# schemat.net
KiCad netlist of a schematic drawn in Altium Designer
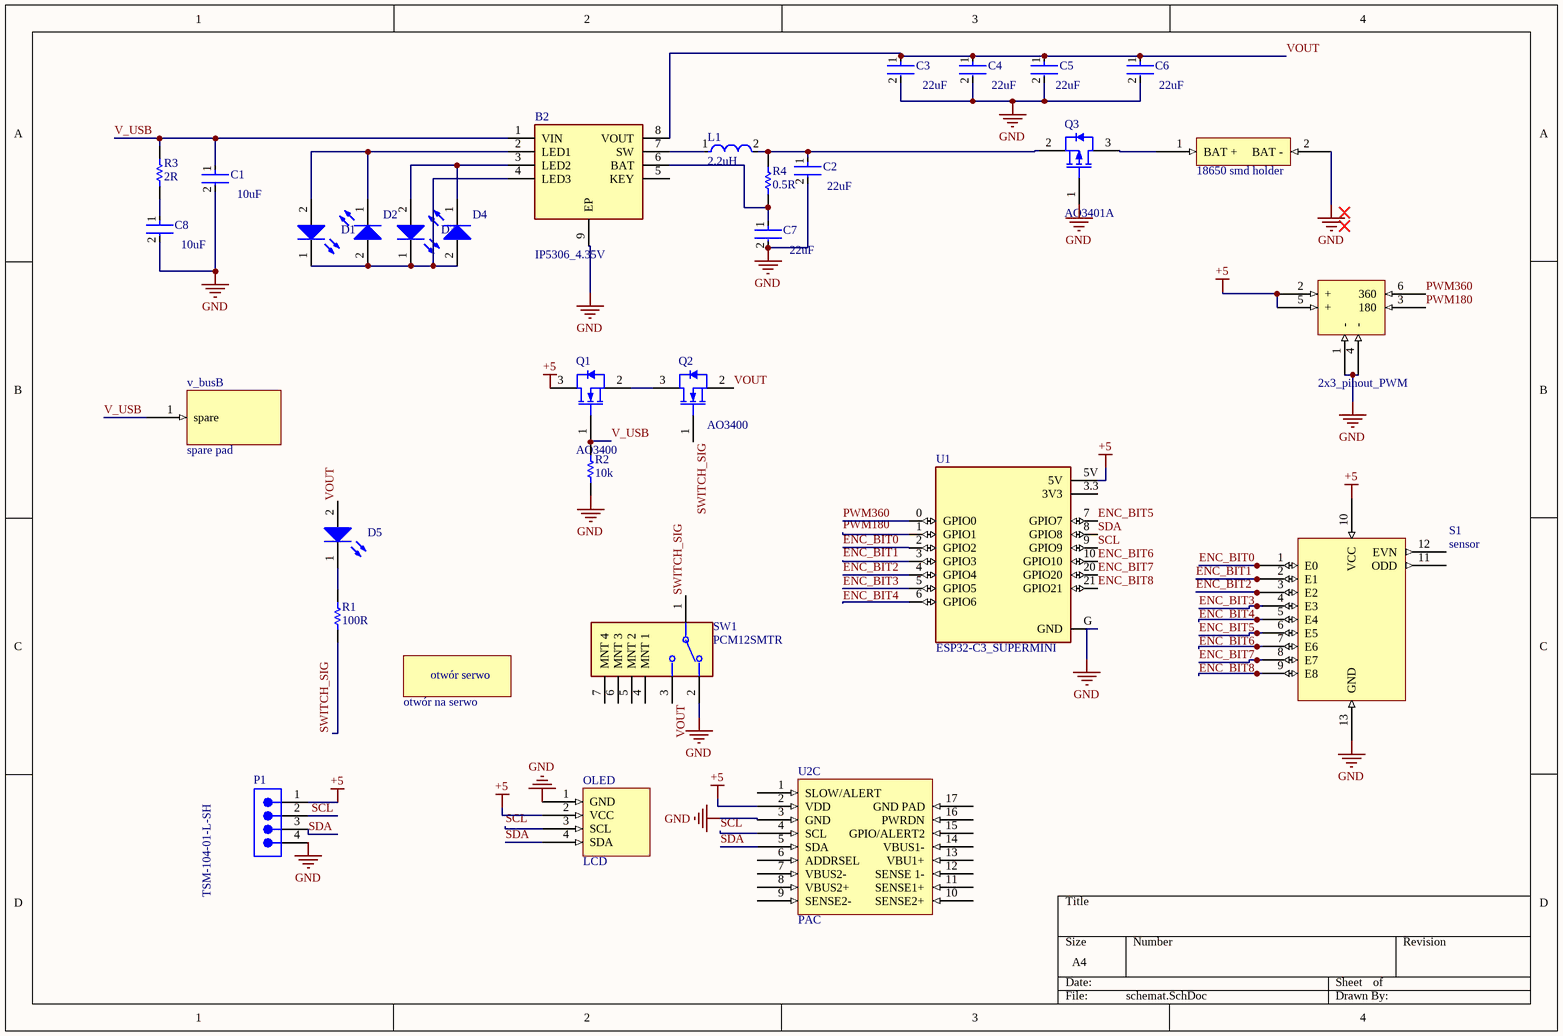
[diagram p0: schemat.SchDoc]

(export (version "E")
  (design (tool "Eeschema 10.0.6"))
  (components
    (comp (ref "*")
      (value "otwór na serwo")
      (footprint "serwo")
      (libsource (lib "biblioteka") (part "otwór na serwo"))
    )
    (comp (ref "B1")
      (value "18650 smd holder")
      (footprint "18650 smd holder")
      (libsource (lib "schematy") (part "18650 smd holder"))
    )
    (comp (ref "B2")
      (value "IP5306_4.35V")
      (footprint "SOIC127P600X165-9N")
      (description "2.1A Charging 2.4 A Discharge Highly Integrated Mobile Power Supply")
      (libsource (lib "IP5306_4.35V") (part "IP5306_4.35V"))
    )
    (comp (ref "C1")
      (value "10uF")
      (footprint "FP-GRM21B-0_15-MFG")
      (description "Chip Multilayer Ceramic Capacitors for General Purpose, 0805, 22uF, X5R, 15%, 20%, 6.3V")
      (fields (field (name "VOLTAGE") "6.3V") (field (name "TOLERANCE") "20%"))
      (libsource (lib "Altium Content Vault") (part "b4654b650e69147ec39a6b967a45e02"))
    )
    (comp (ref "C2")
      (value "22uF")
      (footprint "FP-GRM21B-0_15-MFG")
      (description "Chip Multilayer Ceramic Capacitors for General Purpose, 0805, 22uF, X5R, 15%, 20%, 6.3V")
      (fields (field (name "VOLTAGE") "6.3V") (field (name "TOLERANCE") "20%"))
      (libsource (lib "Altium Content Vault") (part "b4654b650e69147ec39a6b967a45e02"))
    )
    (comp (ref "C3")
      (value "22uF")
      (footprint "FP-GRM21B-0_15-MFG")
      (description "Chip Multilayer Ceramic Capacitors for General Purpose, 0805, 22uF, X5R, 15%, 20%, 6.3V")
      (fields (field (name "VOLTAGE") "6.3V") (field (name "TOLERANCE") "20%"))
      (libsource (lib "Altium Content Vault") (part "b4654b650e69147ec39a6b967a45e02"))
    )
    (comp (ref "C4")
      (value "22uF")
      (footprint "FP-GRM21B-0_15-MFG")
      (description "Chip Multilayer Ceramic Capacitors for General Purpose, 0805, 22uF, X5R, 15%, 20%, 6.3V")
      (fields (field (name "VOLTAGE") "6.3V") (field (name "TOLERANCE") "20%"))
      (libsource (lib "Altium Content Vault") (part "b4654b650e69147ec39a6b967a45e02"))
    )
    (comp (ref "C5")
      (value "22uF")
      (footprint "FP-GRM21B-0_15-MFG")
      (description "Chip Multilayer Ceramic Capacitors for General Purpose, 0805, 22uF, X5R, 15%, 20%, 6.3V")
      (fields (field (name "VOLTAGE") "6.3V") (field (name "TOLERANCE") "20%"))
      (libsource (lib "Altium Content Vault") (part "b4654b650e69147ec39a6b967a45e02"))
    )
    (comp (ref "C6")
      (value "22uF")
      (footprint "FP-GRM21B-0_15-MFG")
      (description "Chip Multilayer Ceramic Capacitors for General Purpose, 0805, 22uF, X5R, 15%, 20%, 6.3V")
      (fields (field (name "VOLTAGE") "6.3V") (field (name "TOLERANCE") "20%"))
      (libsource (lib "Altium Content Vault") (part "b4654b650e69147ec39a6b967a45e02"))
    )
    (comp (ref "C7")
      (value "22uF")
      (footprint "FP-GRM21B-0_15-MFG")
      (description "Chip Multilayer Ceramic Capacitors for General Purpose, 0805, 22uF, X5R, 15%, 20%, 6.3V")
      (fields (field (name "VOLTAGE") "6.3V") (field (name "TOLERANCE") "20%"))
      (libsource (lib "Altium Content Vault") (part "b4654b650e69147ec39a6b967a45e02"))
    )
    (comp (ref "C8")
      (value "10uF")
      (footprint "FP-GRM21B-0_15-MFG")
      (description "Chip Multilayer Ceramic Capacitors for General Purpose, 0805, 22uF, X5R, 15%, 20%, 6.3V")
      (fields (field (name "VOLTAGE") "6.3V") (field (name "TOLERANCE") "20%"))
      (libsource (lib "Altium Content Vault") (part "b4654b650e69147ec39a6b967a45e02"))
    )
    (comp (ref "D1")
      (value "150120BS75000")
      (footprint "WL-SMCW_1206_150120xx75000")
      (libsource (lib "Altium Content Vault") (part "LED_Blue_2A-1K"))
    )
    (comp (ref "D2")
      (value "150120BS75000")
      (footprint "WL-SMCW_1206_150120xx75000")
      (libsource (lib "Altium Content Vault") (part "LED_Blue_2A-1K"))
    )
    (comp (ref "D3")
      (value "150120BS75000")
      (footprint "WL-SMCW_1206_150120xx75000")
      (libsource (lib "Altium Content Vault") (part "LED_Blue_2A-1K"))
    )
    (comp (ref "D4")
      (value "150120BS75000")
      (footprint "WL-SMCW_1206_150120xx75000")
      (libsource (lib "Altium Content Vault") (part "LED_Blue_2A-1K"))
    )
    (comp (ref "D5")
      (value "150120BS75000")
      (footprint "WL-SMCW_1206_150120xx75000")
      (libsource (lib "Altium Content Vault") (part "LED_Blue_2A-1K"))
    )
    (comp (ref "J1")
      (value "2x3_pinout_PWM")
      (footprint "Goldpin raster 2x3")
      (libsource (lib "biblioteka") (part "2x3_pinout_PWM"))
    )
    (comp (ref "L1")
      (value "2.2uH")
      (footprint "FP-ASPI-0630LR-MFG")
      (description "FIXED IND 10UH 4A 68 MOHM SMD")
      (fields (field (name "TOLERANCE") "20%"))
      (libsource (lib "Altium Content Vault") (part "725321dda6339637d4d059423bc1c3c"))
    )
    (comp (ref "OLED") (value "LCD") (footprint "LCD") (libsource (lib "schematy") (part "LCD")))
    (comp (ref "P1")
      (value "TSM-104-01-L-SH")
      (footprint "SMTC-TSM-104-01-X-SH")
      (fields (field (name "MANUFACTURER") "Samtec"))
      (libsource (lib "Altium Content Vault") (part "SMTC-TSM-104-01-X-SH"))
    )
    (comp (ref "Q1")
      (value "AO3400")
      (footprint "AO-SOT23-3_V")
      (description "N-channel Enhancement Mode Field-Effect Transistor; 5.8A/30V")
      (fields (field (name "MANUFACTURER") "Alpha and Omega"))
      (libsource (lib "Altium Content Vault") (part "AO-NEMOS-G1S2D3-3"))
    )
    (comp (ref "Q2")
      (value "AO3400")
      (footprint "AO-SOT23-3_V")
      (description "N-channel Enhancement Mode Field-Effect Transistor; 5.8A/30V")
      (fields (field (name "MANUFACTURER") "Alpha and Omega"))
      (libsource (lib "Altium Content Vault") (part "AO-NEMOS-G1S2D3-3"))
    )
    (comp (ref "Q3")
      (value "AO3401A")
      (footprint "AO-SOT-23-3L_V")
      (description "P-Channel MOSFET, 30 V, 4 A, -55 to 150 degC, 3-Pin SOT-23-3L, RoHS, Tape and Reel")
      (fields (field (name "MANUFACTURER") "Alpha and Omega"))
      (libsource (lib "Altium Content Vault") (part "PEMOS-GSD-3"))
    )
    (comp (ref "R1")
      (value "100R")
      (footprint "RESC2013X50X30LL20T20")
      (fields (field (name "MANUFACTURER") "Vishay Dale") (field (name "PART NUMBER") "CRCW08050000Z0EA"))
      (libsource (lib "Altium Content Vault") (part "RES"))
    )
    (comp (ref "R2")
      (value "10k")
      (footprint "RESC2013X50X30LL20T20")
      (fields (field (name "MANUFACTURER") "Vishay Dale") (field (name "PART NUMBER") "CRCW08050000Z0EA"))
      (libsource (lib "Altium Content Vault") (part "RES"))
    )
    (comp (ref "R3")
      (value "2R")
      (footprint "RESC2013X50X30LL20T20")
      (fields (field (name "MANUFACTURER") "Vishay Dale") (field (name "PART NUMBER") "CRCW08050000Z0EA"))
      (libsource (lib "Altium Content Vault") (part "RES"))
    )
    (comp (ref "R4")
      (value "0.5R")
      (footprint "RESC2013X50X30LL20T20")
      (fields (field (name "MANUFACTURER") "Vishay Dale") (field (name "PART NUMBER") "CRCW08050000Z0EA"))
      (libsource (lib "Altium Content Vault") (part "RES"))
    )
    (comp (ref "S1")
      (value "sensor")
      (footprint "czujnik zbliżeniowy")
      (libsource (lib "schematy") (part "sensor"))
    )
    (comp (ref "SW1")
      (value "PCM12SMTR")
      (footprint "FP-PCM12SMTR-MFG")
      (description "SWITCH SLIDE SPDT 300MA 6V")
      (libsource (lib "Altium Content Vault") (part "1a3f67d7e2b5469b171eeab59ffb4d2"))
    )
    (comp (ref "U1")
      (value "ESP32-C3_SUPERMINI")
      (footprint "MODULE_ESP32-C3_SUPERMINI")
      (description "Super tiny ESP32-C3 board")
      (fields (field (name "MF") "Espressif Systems") (field (name "MP") "ESP32-C3 SuperMini"))
      (libsource (lib "biblioteka") (part "ESP32-C3_SUPERMINI"))
    )
    (comp (ref "U2")
      (value "PAC")
      (footprint "QFN50P300X300X90_HS-17N")
      (libsource (lib "schematy") (part "PAC"))
    )
    (comp (ref "v_bus")
      (value "spare pad")
      (footprint "spare pad")
      (libsource (lib "schematy") (part "spare pad"))
    )
  )
  (nets
    (net (code "1") (name "+5") (class "Default")
      (node (ref "J1") (pin "2") (pinfunction "+_2") (pintype "input"))
      (node (ref "J1") (pin "5") (pinfunction "+_5") (pintype "input"))
      (node (ref "OLED") (pin "2") (pinfunction "VCC_2") (pintype "input"))
      (node (ref "P1") (pin "1") (pinfunction "1_1") (pintype "passive"))
      (node (ref "Q1") (pin "3") (pinfunction "D_3") (pintype "passive"))
      (node (ref "S1") (pin "10") (pinfunction "VCC_10") (pintype "input"))
      (node (ref "U1") (pin "5V") (pinfunction "5V_5V") (pintype "power_in"))
      (node (ref "U2") (pin "2") (pinfunction "VDD_2") (pintype "input"))
    )
    (net (code "2") (name "/ENC_BIT0") (class "Default")
      (node (ref "S1") (pin "1") (pinfunction "E0_1") (pintype "bidirectional"))
      (node (ref "U1") (pin "2") (pinfunction "GPIO2_2") (pintype "bidirectional"))
    )
    (net (code "3") (name "/ENC_BIT1") (class "Default")
      (node (ref "S1") (pin "2") (pinfunction "E1_2") (pintype "bidirectional"))
      (node (ref "U1") (pin "3") (pinfunction "GPIO3_3") (pintype "bidirectional"))
    )
    (net (code "4") (name "/ENC_BIT2") (class "Default")
      (node (ref "S1") (pin "3") (pinfunction "E2_3") (pintype "bidirectional"))
      (node (ref "U1") (pin "4") (pinfunction "GPIO4_4") (pintype "bidirectional"))
    )
    (net (code "5") (name "/ENC_BIT3") (class "Default")
      (node (ref "S1") (pin "4") (pinfunction "E3_4") (pintype "bidirectional"))
      (node (ref "U1") (pin "5") (pinfunction "GPIO5_5") (pintype "bidirectional"))
    )
    (net (code "6") (name "/ENC_BIT4") (class "Default")
      (node (ref "S1") (pin "5") (pinfunction "E4_5") (pintype "bidirectional"))
      (node (ref "U1") (pin "6") (pinfunction "GPIO6_6") (pintype "bidirectional"))
    )
    (net (code "7") (name "/ENC_BIT5") (class "Default")
      (node (ref "S1") (pin "6") (pinfunction "E5_6") (pintype "bidirectional"))
      (node (ref "U1") (pin "7") (pinfunction "GPIO7_7") (pintype "bidirectional"))
    )
    (net (code "8") (name "/ENC_BIT6") (class "Default")
      (node (ref "S1") (pin "7") (pinfunction "E6_7") (pintype "bidirectional"))
      (node (ref "U1") (pin "10") (pinfunction "GPIO10_10") (pintype "bidirectional"))
    )
    (net (code "9") (name "/ENC_BIT7") (class "Default")
      (node (ref "S1") (pin "8") (pinfunction "E7_8") (pintype "bidirectional"))
      (node (ref "U1") (pin "20") (pinfunction "GPIO20_20") (pintype "bidirectional"))
    )
    (net (code "10") (name "/ENC_BIT8") (class "Default")
      (node (ref "S1") (pin "9") (pinfunction "E8_9") (pintype "bidirectional"))
      (node (ref "U1") (pin "21") (pinfunction "GPIO21_21") (pintype "bidirectional"))
    )
    (net (code "11") (name "/PWM180") (class "Default")
      (node (ref "J1") (pin "3") (pinfunction "180_3") (pintype "input"))
      (node (ref "U1") (pin "1") (pinfunction "GPIO1_1") (pintype "bidirectional"))
    )
    (net (code "12") (name "/PWM360") (class "Default")
      (node (ref "J1") (pin "6") (pinfunction "360_6") (pintype "input"))
      (node (ref "U1") (pin "0") (pinfunction "GPIO0_0") (pintype "bidirectional"))
    )
    (net (code "13") (name "/SCL") (class "Default")
      (node (ref "OLED") (pin "3") (pinfunction "SCL_3") (pintype "input"))
      (node (ref "P1") (pin "2") (pinfunction "2_2") (pintype "passive"))
      (node (ref "U1") (pin "9") (pinfunction "GPIO9_9") (pintype "bidirectional"))
      (node (ref "U2") (pin "4") (pinfunction "SCL_4") (pintype "input"))
    )
    (net (code "14") (name "/SDA") (class "Default")
      (node (ref "OLED") (pin "4") (pinfunction "SDA_4") (pintype "input"))
      (node (ref "P1") (pin "3") (pinfunction "3_3") (pintype "passive"))
      (node (ref "U1") (pin "8") (pinfunction "GPIO8_8") (pintype "bidirectional"))
      (node (ref "U2") (pin "5") (pinfunction "SDA_5") (pintype "input"))
    )
    (net (code "15") (name "/SWITCH_SIG") (class "Default")
      (node (ref "Q2") (pin "1") (pinfunction "G_1") (pintype "passive"))
      (node (ref "R1") (pin "2") (pinfunction "2_2") (pintype "passive"))
      (node (ref "SW1") (pin "1") (pinfunction "1_1") (pintype "passive"))
    )
    (net (code "16") (name "/VOUT") (class "Default")
      (node (ref "B2") (pin "8") (pinfunction "VOUT_8") (pintype "passive"))
      (node (ref "C3") (pin "1") (pinfunction "1_1") (pintype "passive"))
      (node (ref "C4") (pin "1") (pinfunction "1_1") (pintype "passive"))
      (node (ref "C5") (pin "1") (pinfunction "1_1") (pintype "passive"))
      (node (ref "C6") (pin "1") (pinfunction "1_1") (pintype "passive"))
      (node (ref "D5") (pin "2") (pinfunction "A_2") (pintype "passive"))
      (node (ref "Q2") (pin "2") (pinfunction "S_2") (pintype "passive"))
      (node (ref "SW1") (pin "3") (pinfunction "3_3") (pintype "passive"))
    )
    (net (code "17") (name "/V_USB") (class "Default")
      (node (ref "B2") (pin "1") (pinfunction "VIN_1") (pintype "passive"))
      (node (ref "C1") (pin "1") (pinfunction "1_1") (pintype "passive"))
      (node (ref "Q1") (pin "1") (pinfunction "G_1") (pintype "passive"))
      (node (ref "R2") (pin "2") (pinfunction "2_2") (pintype "passive"))
      (node (ref "R3") (pin "1") (pinfunction "1_1") (pintype "passive"))
      (node (ref "v_bus") (pin "1") (pinfunction "spare_1") (pintype "input"))
    )
    (net (code "18") (name "GND") (class "Default")
      (node (ref "B1") (pin "2") (pinfunction "BAT_-_2") (pintype "input"))
      (node (ref "B2") (pin "9") (pinfunction "EP_9") (pintype "passive"))
      (node (ref "C1") (pin "2") (pinfunction "2_2") (pintype "passive"))
      (node (ref "C2") (pin "2") (pinfunction "2_2") (pintype "passive"))
      (node (ref "C3") (pin "2") (pinfunction "2_2") (pintype "passive"))
      (node (ref "C4") (pin "2") (pinfunction "2_2") (pintype "passive"))
      (node (ref "C5") (pin "2") (pinfunction "2_2") (pintype "passive"))
      (node (ref "C6") (pin "2") (pinfunction "2_2") (pintype "passive"))
      (node (ref "C7") (pin "2") (pinfunction "2_2") (pintype "passive"))
      (node (ref "C8") (pin "2") (pinfunction "2_2") (pintype "passive"))
      (node (ref "J1") (pin "1") (pinfunction "-_1") (pintype "input"))
      (node (ref "J1") (pin "4") (pinfunction "-_4") (pintype "input"))
      (node (ref "OLED") (pin "1") (pinfunction "GND_1") (pintype "input"))
      (node (ref "Q3") (pin "1") (pinfunction "GATE_1") (pintype "passive"))
      (node (ref "R2") (pin "1") (pinfunction "1_1") (pintype "passive"))
      (node (ref "S1") (pin "13") (pinfunction "GND_13") (pintype "input"))
      (node (ref "SW1") (pin "2") (pinfunction "2_2") (pintype "passive"))
      (node (ref "U1") (pin "G") (pinfunction "GND_G") (pintype "power_in"))
      (node (ref "U2") (pin "3") (pinfunction "GND_3") (pintype "input"))
    )
    (net (code "19") (name "Net-(B1-BAT_+)") (class "Default")
      (node (ref "B1") (pin "1") (pinfunction "BAT_+_1") (pintype "input"))
      (node (ref "Q3") (pin "3") (pinfunction "DRAIN_3") (pintype "passive"))
    )
    (net (code "20") (name "Net-(B2-BAT)") (class "Default")
      (node (ref "B2") (pin "6") (pinfunction "BAT_6") (pintype "passive"))
      (node (ref "C7") (pin "1") (pinfunction "1_1") (pintype "passive"))
      (node (ref "R4") (pin "2") (pinfunction "2_2") (pintype "passive"))
    )
    (net (code "21") (name "Net-(B2-LED1)") (class "Default")
      (node (ref "B2") (pin "2") (pinfunction "LED1_2") (pintype "passive"))
      (node (ref "D1") (pin "2") (pinfunction "A_2") (pintype "passive"))
      (node (ref "D2") (pin "1") (pinfunction "K_1") (pintype "passive"))
    )
    (net (code "22") (name "Net-(B2-LED2)") (class "Default")
      (node (ref "B2") (pin "3") (pinfunction "LED2_3") (pintype "passive"))
      (node (ref "D3") (pin "2") (pinfunction "A_2") (pintype "passive"))
      (node (ref "D4") (pin "1") (pinfunction "K_1") (pintype "passive"))
    )
    (net (code "23") (name "Net-(B2-LED3)") (class "Default")
      (node (ref "B2") (pin "4") (pinfunction "LED3_4") (pintype "passive"))
      (node (ref "D1") (pin "1") (pinfunction "K_1") (pintype "passive"))
      (node (ref "D2") (pin "2") (pinfunction "A_2") (pintype "passive"))
      (node (ref "D3") (pin "1") (pinfunction "K_1") (pintype "passive"))
      (node (ref "D4") (pin "2") (pinfunction "A_2") (pintype "passive"))
    )
    (net (code "24") (name "Net-(B2-SW)") (class "Default")
      (node (ref "B2") (pin "7") (pinfunction "SW_7") (pintype "passive"))
      (node (ref "L1") (pin "1") (pinfunction "1_1") (pintype "passive"))
    )
    (net (code "25") (name "Net-(C8-Pad1)") (class "Default")
      (node (ref "C8") (pin "1") (pinfunction "1_1") (pintype "passive"))
      (node (ref "R3") (pin "2") (pinfunction "2_2") (pintype "passive"))
    )
    (net (code "26") (name "Net-(D5-K)") (class "Default")
      (node (ref "D5") (pin "1") (pinfunction "K_1") (pintype "passive"))
      (node (ref "R1") (pin "1") (pinfunction "1_1") (pintype "passive"))
    )
    (net (code "27") (name "Net-(Q1-S)") (class "Default")
      (node (ref "Q1") (pin "2") (pinfunction "S_2") (pintype "passive"))
      (node (ref "Q2") (pin "3") (pinfunction "D_3") (pintype "passive"))
    )
    (net (code "28") (name "Net-(Q3-SOURCE)") (class "Default")
      (node (ref "C2") (pin "1") (pinfunction "1_1") (pintype "passive"))
      (node (ref "L1") (pin "2") (pinfunction "2_2") (pintype "passive"))
      (node (ref "Q3") (pin "2") (pinfunction "SOURCE_2") (pintype "passive"))
      (node (ref "R4") (pin "1") (pinfunction "1_1") (pintype "passive"))
    )
    (net (code "29") (name "unconnected-(B2-KEY-Pad5)") (class "Default")
      (node (ref "B2") (pin "5") (pinfunction "KEY_5") (pintype "passive"))
    )
    (net (code "30") (name "unconnected-(P1-Pad4)") (class "Default")
      (node (ref "P1") (pin "4") (pinfunction "4_4") (pintype "passive"))
    )
    (net (code "31") (name "unconnected-(S1-EVN-Pad12)") (class "Default")
      (node (ref "S1") (pin "12") (pinfunction "EVN_12") (pintype "output"))
    )
    (net (code "32") (name "unconnected-(S1-ODD-Pad11)") (class "Default")
      (node (ref "S1") (pin "11") (pinfunction "ODD_11") (pintype "output"))
    )
    (net (code "33") (name "unconnected-(SW1-MNT_1-Pad4)") (class "Default")
      (node (ref "SW1") (pin "4") (pinfunction "MNT_1_4") (pintype "passive"))
    )
    (net (code "34") (name "unconnected-(SW1-MNT_2-Pad5)") (class "Default")
      (node (ref "SW1") (pin "5") (pinfunction "MNT_2_5") (pintype "passive"))
    )
    (net (code "35") (name "unconnected-(SW1-MNT_3-Pad6)") (class "Default")
      (node (ref "SW1") (pin "6") (pinfunction "MNT_3_6") (pintype "passive"))
    )
    (net (code "36") (name "unconnected-(SW1-MNT_4-Pad7)") (class "Default")
      (node (ref "SW1") (pin "7") (pinfunction "MNT_4_7") (pintype "passive"))
    )
    (net (code "37") (name "unconnected-(U1-3V3-Pad3.3)") (class "Default")
      (node (ref "U1") (pin "3.3") (pinfunction "3V3_3.3") (pintype "power_in"))
    )
    (net (code "38") (name "unconnected-(U2C-ADDRSEL-Pad6)") (class "Default")
      (node (ref "U2") (pin "6") (pinfunction "ADDRSEL_6") (pintype "input"))
    )
    (net (code "39") (name "unconnected-(U2C-GND_PAD-Pad17)") (class "Default")
      (node (ref "U2") (pin "17") (pinfunction "GND_PAD_17") (pintype "input"))
    )
    (net (code "40") (name "unconnected-(U2C-GPIO{slash}ALERT2-Pad15)") (class "Default")
      (node (ref "U2") (pin "15") (pinfunction "GPIO/ALERT2_15") (pintype "input"))
    )
    (net (code "41") (name "unconnected-(U2C-PWRDN-Pad16)") (class "Default")
      (node (ref "U2") (pin "16") (pinfunction "PWRDN_16") (pintype "input"))
    )
    (net (code "42") (name "unconnected-(U2C-SENSE1+-Pad11)") (class "Default")
      (node (ref "U2") (pin "11") (pinfunction "SENSE1+_11") (pintype "input"))
    )
    (net (code "43") (name "unconnected-(U2C-SENSE2+-Pad10)") (class "Default")
      (node (ref "U2") (pin "10") (pinfunction "SENSE2+_10") (pintype "input"))
    )
    (net (code "44") (name "unconnected-(U2C-SENSE2--Pad9)") (class "Default")
      (node (ref "U2") (pin "9") (pinfunction "SENSE2-_9") (pintype "input"))
    )
    (net (code "45") (name "unconnected-(U2C-SENSE_1--Pad12)") (class "Default")
      (node (ref "U2") (pin "12") (pinfunction "SENSE_1-_12") (pintype "input"))
    )
    (net (code "46") (name "unconnected-(U2C-SLOW{slash}ALERT-Pad1)") (class "Default")
      (node (ref "U2") (pin "1") (pinfunction "SLOW/ALERT_1") (pintype "input"))
    )
    (net (code "47") (name "unconnected-(U2C-VBU1+-Pad13)") (class "Default")
      (node (ref "U2") (pin "13") (pinfunction "VBU1+_13") (pintype "input"))
    )
    (net (code "48") (name "unconnected-(U2C-VBUS1--Pad14)") (class "Default")
      (node (ref "U2") (pin "14") (pinfunction "VBUS1-_14") (pintype "input"))
    )
    (net (code "49") (name "unconnected-(U2C-VBUS2+-Pad8)") (class "Default")
      (node (ref "U2") (pin "8") (pinfunction "VBUS2+_8") (pintype "input"))
    )
    (net (code "50") (name "unconnected-(U2C-VBUS2--Pad7)") (class "Default")
      (node (ref "U2") (pin "7") (pinfunction "VBUS2-_7") (pintype "input"))
    )
  )
)
